# ATmega328p.net
KiCad netlist of a schematic drawn in EAGLE
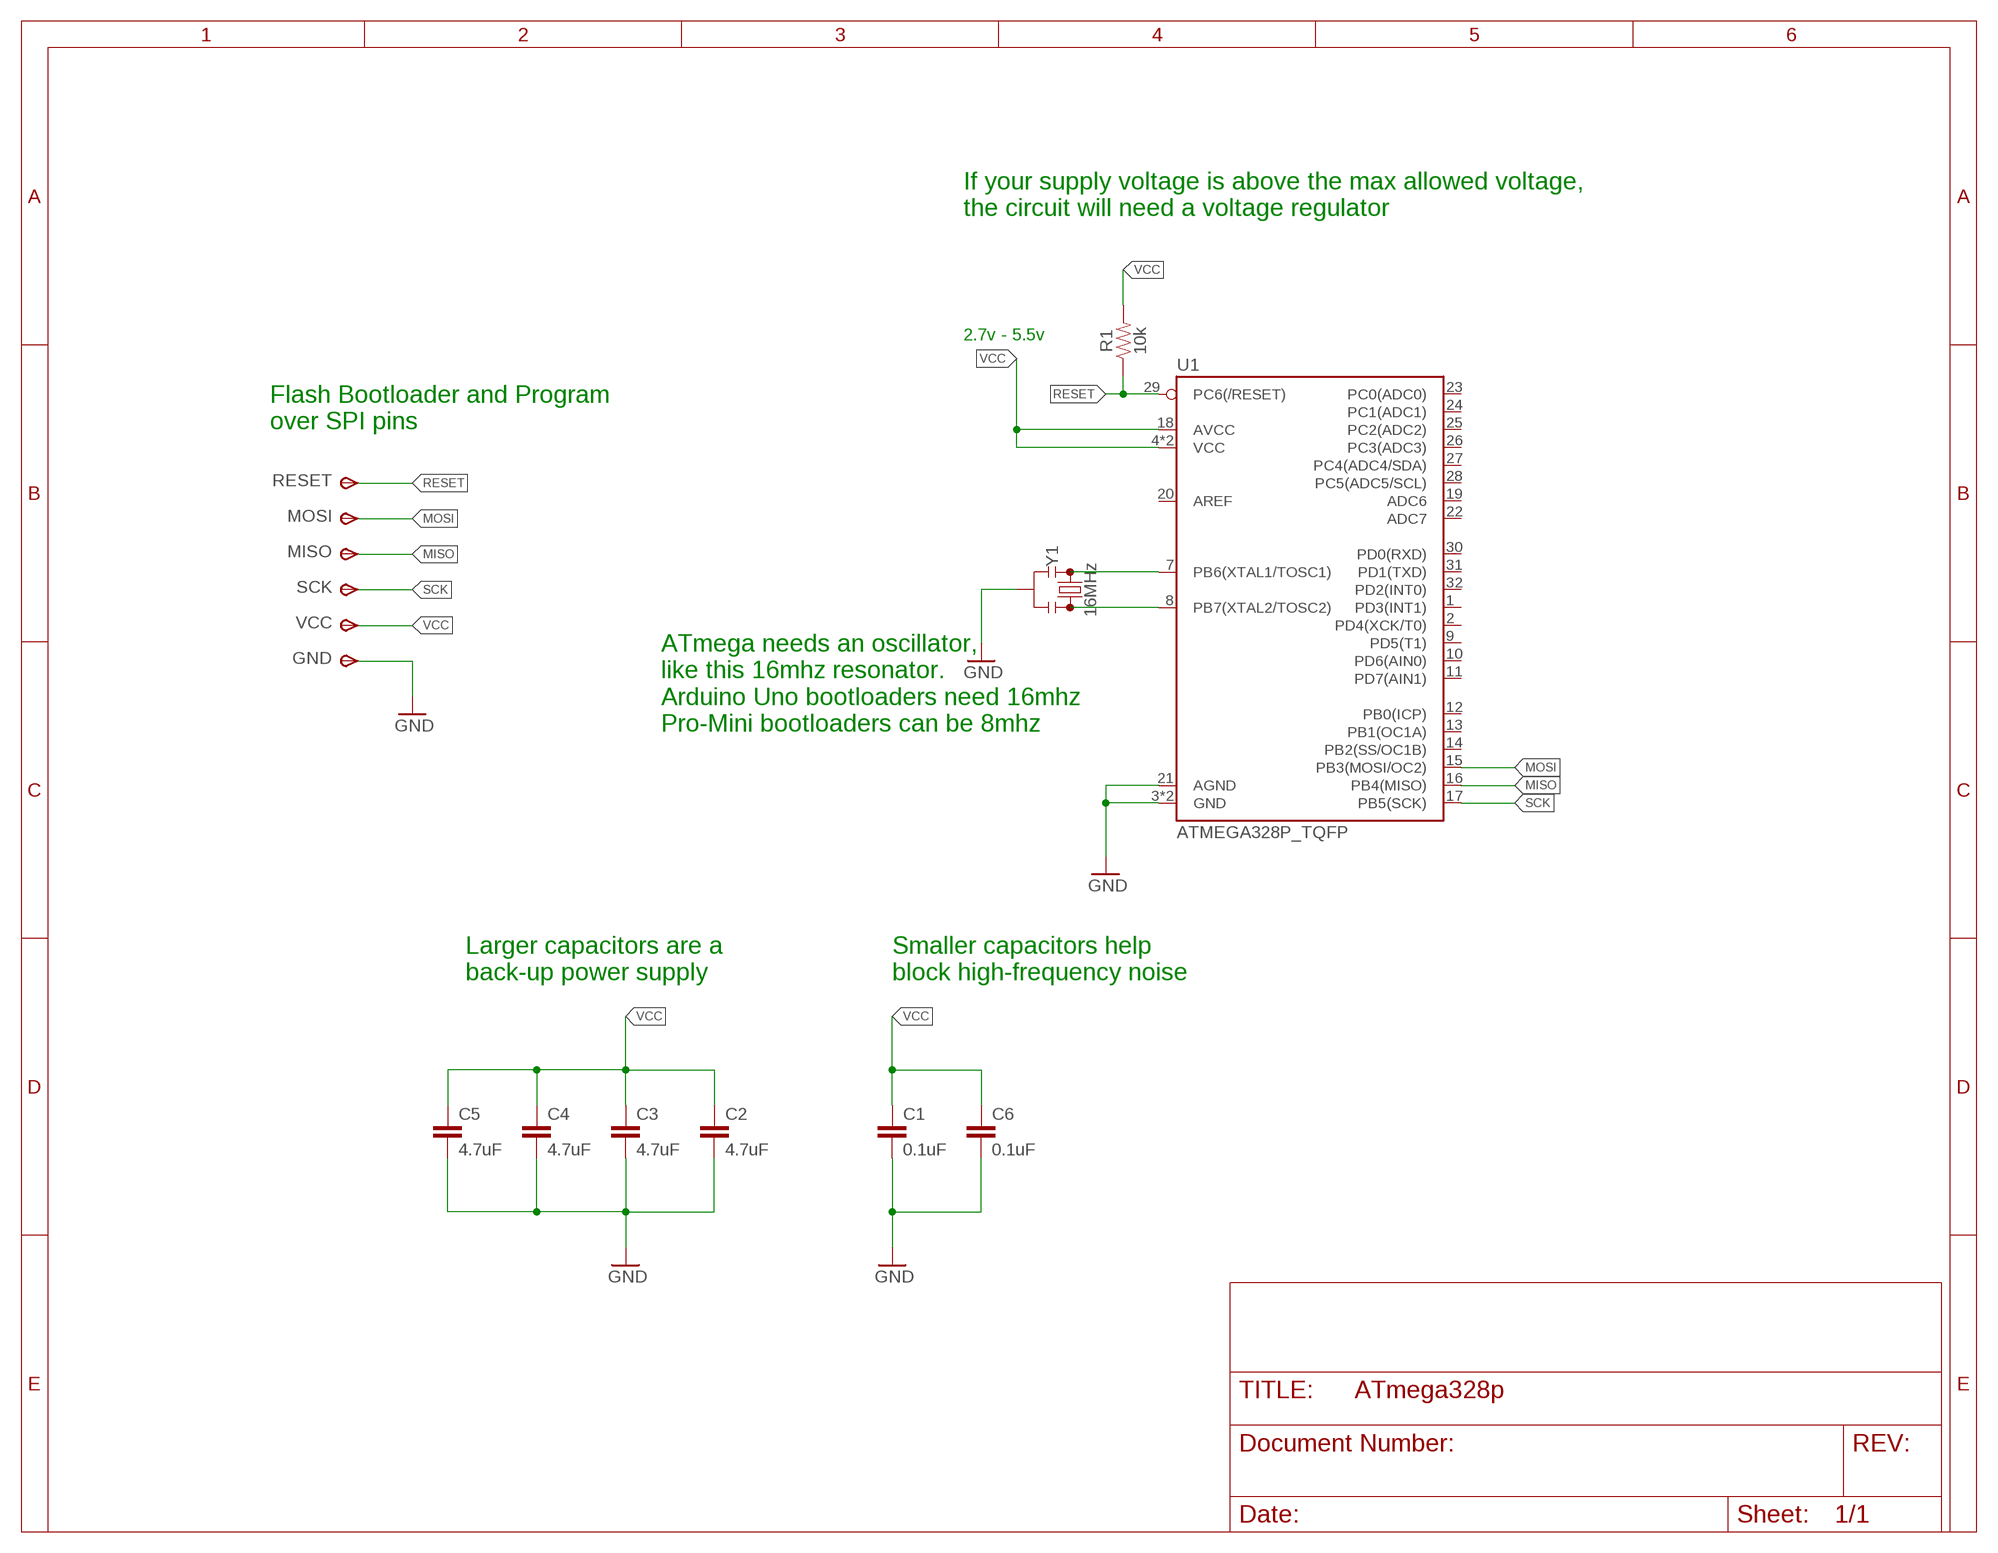
[diagram p0: schematic, sheet 1]

(export (version "E")
  (design (tool "Eeschema 10.0.6"))
  (components
    (comp (ref "C1")
      (value "0.1uF")
      (footprint "eagle-import:0603")
      (libsource (lib "eagle-import") (part "0.1UF-0603-25V-5%"))
    )
    (comp (ref "C2")
      (value "4.7uF")
      (footprint "eagle-import:0603")
      (libsource (lib "eagle-import") (part "4.7UF0603"))
    )
    (comp (ref "C3")
      (value "4.7uF")
      (footprint "eagle-import:0603")
      (libsource (lib "eagle-import") (part "4.7UF0603"))
    )
    (comp (ref "C4")
      (value "4.7uF")
      (footprint "eagle-import:0603")
      (libsource (lib "eagle-import") (part "4.7UF0603"))
    )
    (comp (ref "C5")
      (value "4.7uF")
      (footprint "eagle-import:0603")
      (libsource (lib "eagle-import") (part "4.7UF0603"))
    )
    (comp (ref "C6")
      (value "0.1uF")
      (footprint "eagle-import:0603")
      (libsource (lib "eagle-import") (part "0.1UF-0603-25V-5%"))
    )
    (comp (ref "GND")
      (value "TPSTP14SQ")
      (footprint "eagle-import:TP14SQ")
      (libsource (lib "eagle-import") (part "TPSTP14SQ"))
    )
    (comp (ref "MISO")
      (value "TPSTP14SQ")
      (footprint "eagle-import:TP14SQ")
      (libsource (lib "eagle-import") (part "TPSTP14SQ"))
    )
    (comp (ref "MOSI")
      (value "TPSTP14SQ")
      (footprint "eagle-import:TP14SQ")
      (libsource (lib "eagle-import") (part "TPSTP14SQ"))
    )
    (comp (ref "R1")
      (value "10k")
      (footprint "eagle-import:0603")
      (libsource (lib "eagle-import") (part "10KOHM-0603-1/10W-1%"))
    )
    (comp (ref "RESET")
      (value "TPSTP14SQ")
      (footprint "eagle-import:TP14SQ")
      (libsource (lib "eagle-import") (part "TPSTP14SQ"))
    )
    (comp (ref "SCK")
      (value "TPSTP14SQ")
      (footprint "eagle-import:TP14SQ")
      (libsource (lib "eagle-import") (part "TPSTP14SQ"))
    )
    (comp (ref "U1")
      (value "ATMEGA328P_TQFP")
      (footprint "eagle-import:TQFP32-08")
      (libsource (lib "eagle-import") (part "ATMEGA328P_TQFP"))
    )
    (comp (ref "VCC")
      (value "TPSTP14SQ")
      (footprint "eagle-import:TP14SQ")
      (libsource (lib "eagle-import") (part "TPSTP14SQ"))
    )
    (comp (ref "Y1")
      (value "16MHz")
      (footprint "eagle-import:RESONATOR-SMD-3.2X1.3")
      (libsource (lib "eagle-import") (part "RESONATOR-16MHZSMD_3.2X1.3"))
    )
  )
  (nets
    (net (code "1") (name "GND") (class "Default")
      (node (ref "C1") (pin "2") (pinfunction "2_2") (pintype "passive"))
      (node (ref "C2") (pin "2") (pinfunction "2_2") (pintype "passive"))
      (node (ref "C3") (pin "2") (pinfunction "2_2") (pintype "passive"))
      (node (ref "C4") (pin "2") (pinfunction "2_2") (pintype "passive"))
      (node (ref "C5") (pin "2") (pinfunction "2_2") (pintype "passive"))
      (node (ref "C6") (pin "2") (pinfunction "2_2") (pintype "passive"))
      (node (ref "GND") (pin "TP") (pinfunction "PP_TP") (pintype "input"))
      (node (ref "U1") (pin "21") (pinfunction "AGND_21") (pintype "bidirectional"))
      (node (ref "U1") (pin "3") (pinfunction "GND_3") (pintype "bidirectional"))
      (node (ref "U1") (pin "5") (pinfunction "GND_5") (pintype "bidirectional"))
      (node (ref "Y1") (pin "2") (pinfunction "2_2") (pintype "passive"))
    )
    (net (code "2") (name "MISO") (class "Default")
      (node (ref "MISO") (pin "TP") (pinfunction "PP_TP") (pintype "input"))
      (node (ref "U1") (pin "16") (pinfunction "PB4(MISO)_16") (pintype "bidirectional"))
    )
    (net (code "3") (name "MOSI") (class "Default")
      (node (ref "MOSI") (pin "TP") (pinfunction "PP_TP") (pintype "input"))
      (node (ref "U1") (pin "15") (pinfunction "PB3(MOSI/OC2)_15") (pintype "bidirectional"))
    )
    (net (code "4") (name "Net-(U1-PB6(XTAL1{slash}TOSC1))") (class "Default")
      (node (ref "U1") (pin "7") (pinfunction "PB6(XTAL1/TOSC1)_7") (pintype "bidirectional"))
      (node (ref "Y1") (pin "1") (pinfunction "1_1") (pintype "passive"))
    )
    (net (code "5") (name "Net-(U1-PB7(XTAL2{slash}TOSC2))") (class "Default")
      (node (ref "U1") (pin "8") (pinfunction "PB7(XTAL2/TOSC2)_8") (pintype "bidirectional"))
      (node (ref "Y1") (pin "3") (pinfunction "3_3") (pintype "passive"))
    )
    (net (code "6") (name "RESET") (class "Default")
      (node (ref "R1") (pin "1") (pinfunction "1_1") (pintype "passive"))
      (node (ref "RESET") (pin "TP") (pinfunction "PP_TP") (pintype "input"))
      (node (ref "U1") (pin "29") (pinfunction "PC6(/RESET)_29") (pintype "bidirectional"))
    )
    (net (code "7") (name "SCK") (class "Default")
      (node (ref "SCK") (pin "TP") (pinfunction "PP_TP") (pintype "input"))
      (node (ref "U1") (pin "17") (pinfunction "PB5(SCK)_17") (pintype "bidirectional"))
    )
    (net (code "8") (name "VCC") (class "Default")
      (node (ref "C1") (pin "1") (pinfunction "1_1") (pintype "passive"))
      (node (ref "C2") (pin "1") (pinfunction "1_1") (pintype "passive"))
      (node (ref "C3") (pin "1") (pinfunction "1_1") (pintype "passive"))
      (node (ref "C4") (pin "1") (pinfunction "1_1") (pintype "passive"))
      (node (ref "C5") (pin "1") (pinfunction "1_1") (pintype "passive"))
      (node (ref "C6") (pin "1") (pinfunction "1_1") (pintype "passive"))
      (node (ref "R1") (pin "2") (pinfunction "2_2") (pintype "passive"))
      (node (ref "U1") (pin "18") (pinfunction "AVCC_18") (pintype "bidirectional"))
      (node (ref "U1") (pin "4") (pinfunction "VCC_4") (pintype "bidirectional"))
      (node (ref "U1") (pin "6") (pinfunction "VCC_6") (pintype "bidirectional"))
      (node (ref "VCC") (pin "TP") (pinfunction "PP_TP") (pintype "input"))
    )
    (net (code "9") (name "unconnected-(U1-ADC6-Pad19)") (class "Default")
      (node (ref "U1") (pin "19") (pinfunction "ADC6_19") (pintype "bidirectional"))
    )
    (net (code "10") (name "unconnected-(U1-ADC7-Pad22)") (class "Default")
      (node (ref "U1") (pin "22") (pinfunction "ADC7_22") (pintype "bidirectional"))
    )
    (net (code "11") (name "unconnected-(U1-AREF-Pad20)") (class "Default")
      (node (ref "U1") (pin "20") (pinfunction "AREF_20") (pintype "bidirectional"))
    )
    (net (code "12") (name "unconnected-(U1-PB0(ICP)-Pad12)") (class "Default")
      (node (ref "U1") (pin "12") (pinfunction "PB0(ICP)_12") (pintype "bidirectional"))
    )
    (net (code "13") (name "unconnected-(U1-PB1(OC1A)-Pad13)") (class "Default")
      (node (ref "U1") (pin "13") (pinfunction "PB1(OC1A)_13") (pintype "bidirectional"))
    )
    (net (code "14") (name "unconnected-(U1-PB2(SS{slash}OC1B)-Pad14)") (class "Default")
      (node (ref "U1") (pin "14") (pinfunction "PB2(SS/OC1B)_14") (pintype "bidirectional"))
    )
    (net (code "15") (name "unconnected-(U1-PC0(ADC0)-Pad23)") (class "Default")
      (node (ref "U1") (pin "23") (pinfunction "PC0(ADC0)_23") (pintype "bidirectional"))
    )
    (net (code "16") (name "unconnected-(U1-PC1(ADC1)-Pad24)") (class "Default")
      (node (ref "U1") (pin "24") (pinfunction "PC1(ADC1)_24") (pintype "bidirectional"))
    )
    (net (code "17") (name "unconnected-(U1-PC2(ADC2)-Pad25)") (class "Default")
      (node (ref "U1") (pin "25") (pinfunction "PC2(ADC2)_25") (pintype "bidirectional"))
    )
    (net (code "18") (name "unconnected-(U1-PC3(ADC3)-Pad26)") (class "Default")
      (node (ref "U1") (pin "26") (pinfunction "PC3(ADC3)_26") (pintype "bidirectional"))
    )
    (net (code "19") (name "unconnected-(U1-PC4(ADC4{slash}SDA)-Pad27)") (class "Default")
      (node (ref "U1") (pin "27") (pinfunction "PC4(ADC4/SDA)_27") (pintype "bidirectional"))
    )
    (net (code "20") (name "unconnected-(U1-PC5(ADC5{slash}SCL)-Pad28)") (class "Default")
      (node (ref "U1") (pin "28") (pinfunction "PC5(ADC5/SCL)_28") (pintype "bidirectional"))
    )
    (net (code "21") (name "unconnected-(U1-PD0(RXD)-Pad30)") (class "Default")
      (node (ref "U1") (pin "30") (pinfunction "PD0(RXD)_30") (pintype "bidirectional"))
    )
    (net (code "22") (name "unconnected-(U1-PD1(TXD)-Pad31)") (class "Default")
      (node (ref "U1") (pin "31") (pinfunction "PD1(TXD)_31") (pintype "bidirectional"))
    )
    (net (code "23") (name "unconnected-(U1-PD2(INT0)-Pad32)") (class "Default")
      (node (ref "U1") (pin "32") (pinfunction "PD2(INT0)_32") (pintype "bidirectional"))
    )
    (net (code "24") (name "unconnected-(U1-PD3(INT1)-Pad1)") (class "Default")
      (node (ref "U1") (pin "1") (pinfunction "PD3(INT1)_1") (pintype "bidirectional"))
    )
    (net (code "25") (name "unconnected-(U1-PD4(XCK{slash}T0)-Pad2)") (class "Default")
      (node (ref "U1") (pin "2") (pinfunction "PD4(XCK/T0)_2") (pintype "bidirectional"))
    )
    (net (code "26") (name "unconnected-(U1-PD5(T1)-Pad9)") (class "Default")
      (node (ref "U1") (pin "9") (pinfunction "PD5(T1)_9") (pintype "bidirectional"))
    )
    (net (code "27") (name "unconnected-(U1-PD6(AIN0)-Pad10)") (class "Default")
      (node (ref "U1") (pin "10") (pinfunction "PD6(AIN0)_10") (pintype "bidirectional"))
    )
    (net (code "28") (name "unconnected-(U1-PD7(AIN1)-Pad11)") (class "Default")
      (node (ref "U1") (pin "11") (pinfunction "PD7(AIN1)_11") (pintype "bidirectional"))
    )
  )
)
